# VOLTAGE_REFERENCE.net
KiCad netlist of a schematic drawn in Altium Designer
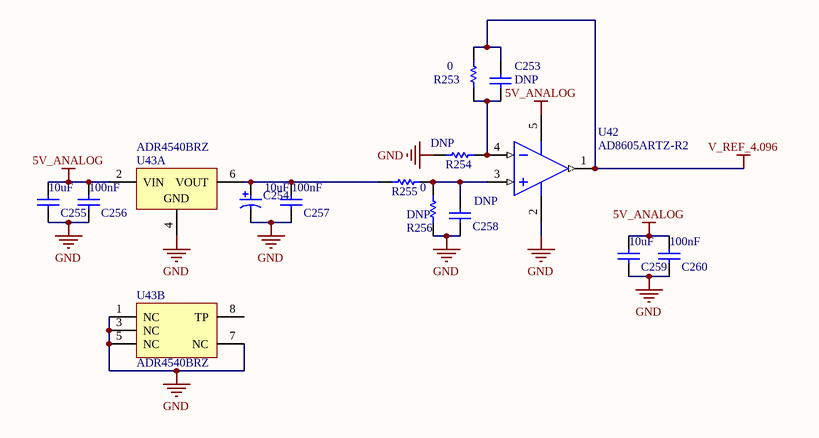
[diagram p0: VOLTAGE_REFERENCE.SchDoc]

(export (version "E")
  (design (tool "Eeschema 10.0.6"))
  (components
    (comp (ref "C253")
      (value "DNP")
      (footprint "CAPC0402(1005)60_L")
      (description "0402 (1005 Metric) Chip Capacitor")
      (fields (field (name "Comment") "CAP0402"))
      (libsource (lib "Altium Content Vault") (part "CMP-1590-00004-1"))
    )
    (comp (ref "C254")
      (value "T491A106K016AT")
      (footprint "KEMT-A-3216-18-2_M")
      (description "Capacitor, Tantalum, 10 uF, +/- 10%, 16 V, -55 to 125 degC, 2-Pin SMD (1206), RoHS, Tape and Reel")
      (fields
        (field (name "VOLTAGE") "16VDC")
        (field (name "CAPACITANCE") "10uF")
        (field (name "MANUFACTURER") "Kemet")
      )
      (libsource (lib "Altium Content Vault") (part "CMP-2000-05173-1"))
    )
    (comp (ref "C255")
      (value "10uF")
      (footprint "CAPC0805(2012)145_L")
      (description "0805 (2012 Metric) Chip Capacitor")
      (fields (field (name "Comment") "CAP0805"))
      (libsource (lib "Altium Content Vault") (part "CMP-1590-00003-1"))
    )
    (comp (ref "C256")
      (value "100nF")
      (footprint "CAPC0402(1005)60_L")
      (description "0402 (1005 Metric) Chip Capacitor")
      (fields (field (name "Comment") "CAP0402"))
      (libsource (lib "Altium Content Vault") (part "CMP-1590-00004-1"))
    )
    (comp (ref "C257")
      (value "100nF")
      (footprint "CAPC0402(1005)60_L")
      (description "0402 (1005 Metric) Chip Capacitor")
      (fields (field (name "Comment") "CAP0402"))
      (libsource (lib "Altium Content Vault") (part "CMP-1590-00004-1"))
    )
    (comp (ref "C258")
      (value "DNP")
      (footprint "CAPC0402(1005)60_L")
      (description "0402 (1005 Metric) Chip Capacitor")
      (fields (field (name "Comment") "CAP0402"))
      (libsource (lib "Altium Content Vault") (part "CMP-1590-00004-1"))
    )
    (comp (ref "C259")
      (value "10uF")
      (footprint "CAPC0805(2012)145_L")
      (description "0805 (2012 Metric) Chip Capacitor")
      (fields (field (name "Comment") "CAP0805"))
      (libsource (lib "Altium Content Vault") (part "CMP-1590-00003-1"))
    )
    (comp (ref "C260")
      (value "100nF")
      (footprint "CAPC0402(1005)60_L")
      (description "0402 (1005 Metric) Chip Capacitor")
      (fields (field (name "Comment") "CAP0402"))
      (libsource (lib "Altium Content Vault") (part "CMP-1590-00004-1"))
    )
    (comp (ref "R253")
      (value "0")
      (footprint "RESC0402(1005)_L")
      (description "0402 (1005 Metric) Chip Resistor")
      (fields (field (name "Comment") "RES0402"))
      (libsource (lib "Altium Content Vault") (part "CMP-1591-00004-1"))
    )
    (comp (ref "R254")
      (value "DNP")
      (footprint "RESC0402(1005)_L")
      (description "0402 (1005 Metric) Chip Resistor")
      (fields (field (name "Comment") "RES0402"))
      (libsource (lib "Altium Content Vault") (part "CMP-1591-00004-1"))
    )
    (comp (ref "R255")
      (value "0")
      (footprint "RESC0402(1005)_L")
      (description "0402 (1005 Metric) Chip Resistor")
      (fields (field (name "Comment") "RES0402"))
      (libsource (lib "Altium Content Vault") (part "CMP-1591-00004-1"))
    )
    (comp (ref "R256")
      (value "DNP")
      (footprint "RESC0402(1005)_L")
      (description "0402 (1005 Metric) Chip Resistor")
      (fields (field (name "Comment") "RES0402"))
      (libsource (lib "Altium Content Vault") (part "CMP-1591-00004-1"))
    )
    (comp (ref "U42")
      (value "AD8605ARTZ-R2")
      (footprint "ADI-RJ-5_L")
      (fields (field (name "GENERIC PART NUMBER") "AD8605") (field (name "MANUFACTURER") "Analog Devices"))
      (libsource (lib "Altium Content Vault") (part "ADI-ADxxxx-X-5"))
    )
    (comp (ref "U43")
      (value "ADR4540BRZ")
      (footprint "ADI-R-8_M")
      (fields (field (name "MANUFACTURER") "Analog Devices"))
      (libsource (lib "Altium Content Vault") (part "ADI-ADR45xx-R-8"))
    )
  )
  (nets
    (net (code "1") (name "5V_ANALOG") (class "Default")
      (node (ref "C255") (pin "2") (pinfunction "2_2") (pintype "passive"))
      (node (ref "C256") (pin "1") (pinfunction "1_1") (pintype "passive"))
      (node (ref "C259") (pin "2") (pinfunction "2_2") (pintype "passive"))
      (node (ref "C260") (pin "1") (pinfunction "1_1") (pintype "passive"))
      (node (ref "U42") (pin "5") (pinfunction "+V_5") (pintype "power_in"))
      (node (ref "U43") (pin "2") (pinfunction "VIN_2") (pintype "power_in"))
    )
    (net (code "2") (name "GND") (class "Default")
      (node (ref "C254") (pin "2") (pinfunction "2_2") (pintype "passive"))
      (node (ref "C255") (pin "1") (pinfunction "1_1") (pintype "passive"))
      (node (ref "C256") (pin "2") (pinfunction "2_2") (pintype "passive"))
      (node (ref "C257") (pin "2") (pinfunction "2_2") (pintype "passive"))
      (node (ref "C258") (pin "2") (pinfunction "2_2") (pintype "passive"))
      (node (ref "C259") (pin "1") (pinfunction "1_1") (pintype "passive"))
      (node (ref "C260") (pin "2") (pinfunction "2_2") (pintype "passive"))
      (node (ref "R254") (pin "1") (pinfunction "1_1") (pintype "passive"))
      (node (ref "R256") (pin "2") (pinfunction "2_2") (pintype "passive"))
      (node (ref "U42") (pin "2") (pinfunction "-V_2") (pintype "power_in"))
      (node (ref "U43") (pin "1") (pinfunction "NC_1") (pintype "passive"))
      (node (ref "U43") (pin "3") (pinfunction "NC_3") (pintype "passive"))
      (node (ref "U43") (pin "4") (pinfunction "GND_4") (pintype "power_in"))
      (node (ref "U43") (pin "5") (pinfunction "NC_5") (pintype "passive"))
      (node (ref "U43") (pin "7") (pinfunction "NC_7") (pintype "passive"))
    )
    (net (code "3") (name "Net-(U42-+IN)") (class "Default")
      (node (ref "C258") (pin "1") (pinfunction "1_1") (pintype "passive"))
      (node (ref "R255") (pin "2") (pinfunction "2_2") (pintype "passive"))
      (node (ref "R256") (pin "1") (pinfunction "1_1") (pintype "passive"))
      (node (ref "U42") (pin "3") (pinfunction "+IN_3") (pintype "input"))
    )
    (net (code "4") (name "Net-(U42--IN)") (class "Default")
      (node (ref "C253") (pin "2") (pinfunction "2_2") (pintype "passive"))
      (node (ref "R253") (pin "2") (pinfunction "2_2") (pintype "passive"))
      (node (ref "R254") (pin "2") (pinfunction "2_2") (pintype "passive"))
      (node (ref "U42") (pin "4") (pinfunction "-IN_4") (pintype "input"))
    )
    (net (code "5") (name "Net-(U43A-VOUT)") (class "Default")
      (node (ref "C254") (pin "1") (pinfunction "1_1") (pintype "passive"))
      (node (ref "C257") (pin "1") (pinfunction "1_1") (pintype "passive"))
      (node (ref "R255") (pin "1") (pinfunction "1_1") (pintype "passive"))
      (node (ref "U43") (pin "6") (pinfunction "VOUT_6") (pintype "power_in"))
    )
    (net (code "6") (name "V_REF_4.096") (class "Default")
      (node (ref "C253") (pin "1") (pinfunction "1_1") (pintype "passive"))
      (node (ref "R253") (pin "1") (pinfunction "1_1") (pintype "passive"))
      (node (ref "U42") (pin "1") (pinfunction "OUT_1") (pintype "output"))
    )
    (net (code "7") (name "unconnected-(U43B-TP-Pad8)") (class "Default")
      (node (ref "U43") (pin "8") (pinfunction "TP_8") (pintype "passive"))
    )
  )
)
